# LPF_pcb.net
KiCad netlist of a schematic drawn in EAGLE
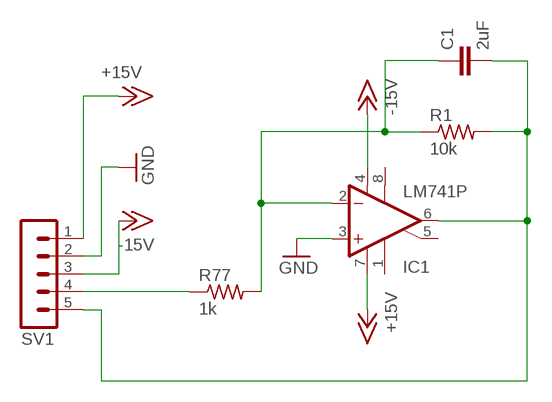
[diagram p0: schematic, sheet 1]

(export (version "E")
  (design (tool "Eeschema 10.0.6"))
  (components
    (comp (ref "C1")
      (value "2uF")
      (footprint "eagle-import:C0603")
      (libsource (lib "eagle-import") (part "C-EUC0603"))
    )
    (comp (ref "IC1")
      (value "LM741P")
      (footprint "eagle-import:DIL08")
      (libsource (lib "eagle-import") (part "741PLM"))
    )
    (comp (ref "R1")
      (value "10k")
      (footprint "eagle-import:R0603")
      (libsource (lib "eagle-import") (part "R-US_R0603"))
    )
    (comp (ref "R77")
      (value "1k")
      (footprint "eagle-import:R0603")
      (libsource (lib "eagle-import") (part "R-US_R0603"))
    )
    (comp (ref "SV1")
      (value "MA05-1")
      (footprint "eagle-import:MA05-1")
      (libsource (lib "eagle-import") (part "MA05-1"))
    )
  )
  (nets
    (net (code "1") (name "+15V") (class "Default")
      (node (ref "IC1") (pin "7") (pinfunction "V+_7") (pintype "power_in"))
      (node (ref "SV1") (pin "1") (pinfunction "1_1") (pintype "passive"))
    )
    (net (code "2") (name "-15V") (class "Default")
      (node (ref "IC1") (pin "4") (pinfunction "V-_4") (pintype "power_in"))
      (node (ref "SV1") (pin "3") (pinfunction "3_3") (pintype "passive"))
    )
    (net (code "3") (name "GND") (class "Default")
      (node (ref "IC1") (pin "3") (pinfunction "+IN_3") (pintype "input"))
      (node (ref "SV1") (pin "2") (pinfunction "2_2") (pintype "passive"))
    )
    (net (code "4") (name "Net-(IC1--IN)") (class "Default")
      (node (ref "C1") (pin "1") (pinfunction "1_1") (pintype "passive"))
      (node (ref "IC1") (pin "2") (pinfunction "-IN_2") (pintype "input"))
      (node (ref "R1") (pin "1") (pinfunction "1_1") (pintype "passive"))
      (node (ref "R77") (pin "2") (pinfunction "2_2") (pintype "passive"))
    )
    (net (code "5") (name "Net-(IC1-OUT)") (class "Default")
      (node (ref "C1") (pin "2") (pinfunction "2_2") (pintype "passive"))
      (node (ref "IC1") (pin "6") (pinfunction "OUT_6") (pintype "output"))
      (node (ref "R1") (pin "2") (pinfunction "2_2") (pintype "passive"))
      (node (ref "SV1") (pin "5") (pinfunction "5_5") (pintype "passive"))
    )
    (net (code "6") (name "Net-(R77-Pad1)") (class "Default")
      (node (ref "R77") (pin "1") (pinfunction "1_1") (pintype "passive"))
      (node (ref "SV1") (pin "4") (pinfunction "4_4") (pintype "passive"))
    )
    (net (code "7") (name "unconnected-(IC1-ON1-Pad1)") (class "Default")
      (node (ref "IC1") (pin "1") (pinfunction "ON1_1") (pintype "passive"))
    )
    (net (code "8") (name "unconnected-(IC1-ON2-Pad5)") (class "Default")
      (node (ref "IC1") (pin "5") (pinfunction "ON2_5") (pintype "passive"))
    )
    (net (code "9") (name "unconnected-(IC1-OPT-Pad8)") (class "Default")
      (node (ref "IC1") (pin "8") (pinfunction "OPT_8") (pintype "passive"))
    )
  )
)
